# Smart_Driver_Adapter_PadMod.net
KiCad netlist of a schematic drawn in EAGLE
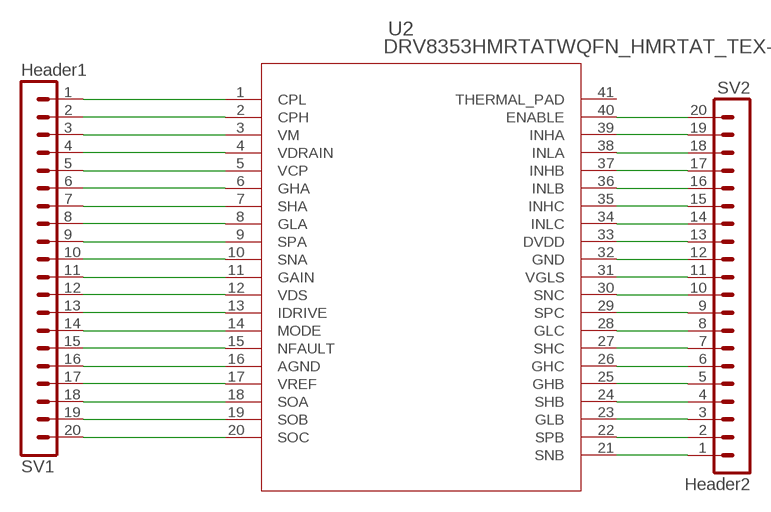
[diagram p0: schematic, sheet 1]

(export (version "E")
  (design (tool "Eeschema 10.0.6"))
  (components
    (comp (ref "SV1")
      (value "Header1")
      (footprint "eagle-import:MA20-1")
      (libsource (lib "eagle-import") (part "MA20-1"))
    )
    (comp (ref "SV2")
      (value "Header2")
      (footprint "eagle-import:MA20-1")
      (libsource (lib "eagle-import") (part "MA20-1"))
    )
    (comp (ref "U2")
      (value "DRV8353HMRTATWQFN_HMRTAT_TEX-M")
      (footprint "eagle-import:WQFN_HMRTAT_TEX-M")
      (fields
        (field (name "MANUFACTURER_PART_NUMBER") "DRV8353HMRTAT")
        (field (name "COPYRIGHT") "Copyright (C) 2021 Ultra Librarian. All rights reserved.")
      )
      (libsource (lib "eagle-import") (part "DRV8353HMRTATWQFN_HMRTAT_TEX-M"))
    )
  )
  (nets
    (net (code "1") (name "Net-(U2-AGND)") (class "Default")
      (node (ref "SV1") (pin "16") (pinfunction "16_16") (pintype "passive"))
      (node (ref "U2") (pin "16") (pinfunction "AGND_16") (pintype "passive"))
    )
    (net (code "2") (name "Net-(U2-CPH)") (class "Default")
      (node (ref "SV1") (pin "2") (pinfunction "2_2") (pintype "passive"))
      (node (ref "U2") (pin "2") (pinfunction "CPH_2") (pintype "passive"))
    )
    (net (code "3") (name "Net-(U2-CPL)") (class "Default")
      (node (ref "SV1") (pin "1") (pinfunction "1_1") (pintype "passive"))
      (node (ref "U2") (pin "1") (pinfunction "CPL_1") (pintype "passive"))
    )
    (net (code "4") (name "Net-(U2-DVDD)") (class "Default")
      (node (ref "SV2") (pin "13") (pinfunction "13_13") (pintype "passive"))
      (node (ref "U2") (pin "33") (pinfunction "DVDD_33") (pintype "power_in"))
    )
    (net (code "5") (name "Net-(U2-ENABLE)") (class "Default")
      (node (ref "SV2") (pin "20") (pinfunction "20_20") (pintype "passive"))
      (node (ref "U2") (pin "40") (pinfunction "ENABLE_40") (pintype "passive"))
    )
    (net (code "6") (name "Net-(U2-GAIN)") (class "Default")
      (node (ref "SV1") (pin "11") (pinfunction "11_11") (pintype "passive"))
      (node (ref "U2") (pin "11") (pinfunction "GAIN_11") (pintype "passive"))
    )
    (net (code "7") (name "Net-(U2-GHA)") (class "Default")
      (node (ref "SV1") (pin "6") (pinfunction "6_6") (pintype "passive"))
      (node (ref "U2") (pin "6") (pinfunction "GHA_6") (pintype "passive"))
    )
    (net (code "8") (name "Net-(U2-GHB)") (class "Default")
      (node (ref "SV2") (pin "5") (pinfunction "5_5") (pintype "passive"))
      (node (ref "U2") (pin "25") (pinfunction "GHB_25") (pintype "passive"))
    )
    (net (code "9") (name "Net-(U2-GHC)") (class "Default")
      (node (ref "SV2") (pin "6") (pinfunction "6_6") (pintype "passive"))
      (node (ref "U2") (pin "26") (pinfunction "GHC_26") (pintype "passive"))
    )
    (net (code "10") (name "Net-(U2-GLA)") (class "Default")
      (node (ref "SV1") (pin "8") (pinfunction "8_8") (pintype "passive"))
      (node (ref "U2") (pin "8") (pinfunction "GLA_8") (pintype "passive"))
    )
    (net (code "11") (name "Net-(U2-GLB)") (class "Default")
      (node (ref "SV2") (pin "3") (pinfunction "3_3") (pintype "passive"))
      (node (ref "U2") (pin "23") (pinfunction "GLB_23") (pintype "passive"))
    )
    (net (code "12") (name "Net-(U2-GLC)") (class "Default")
      (node (ref "SV2") (pin "8") (pinfunction "8_8") (pintype "passive"))
      (node (ref "U2") (pin "28") (pinfunction "GLC_28") (pintype "passive"))
    )
    (net (code "13") (name "Net-(U2-GND)") (class "Default")
      (node (ref "SV2") (pin "12") (pinfunction "12_12") (pintype "passive"))
      (node (ref "U2") (pin "32") (pinfunction "GND_32") (pintype "passive"))
    )
    (net (code "14") (name "Net-(U2-IDRIVE)") (class "Default")
      (node (ref "SV1") (pin "13") (pinfunction "13_13") (pintype "passive"))
      (node (ref "U2") (pin "13") (pinfunction "IDRIVE_13") (pintype "passive"))
    )
    (net (code "15") (name "Net-(U2-INHA)") (class "Default")
      (node (ref "SV2") (pin "19") (pinfunction "19_19") (pintype "passive"))
      (node (ref "U2") (pin "39") (pinfunction "INHA_39") (pintype "input"))
    )
    (net (code "16") (name "Net-(U2-INHB)") (class "Default")
      (node (ref "SV2") (pin "17") (pinfunction "17_17") (pintype "passive"))
      (node (ref "U2") (pin "37") (pinfunction "INHB_37") (pintype "input"))
    )
    (net (code "17") (name "Net-(U2-INHC)") (class "Default")
      (node (ref "SV2") (pin "15") (pinfunction "15_15") (pintype "passive"))
      (node (ref "U2") (pin "35") (pinfunction "INHC_35") (pintype "input"))
    )
    (net (code "18") (name "Net-(U2-INLA)") (class "Default")
      (node (ref "SV2") (pin "18") (pinfunction "18_18") (pintype "passive"))
      (node (ref "U2") (pin "38") (pinfunction "INLA_38") (pintype "input"))
    )
    (net (code "19") (name "Net-(U2-INLB)") (class "Default")
      (node (ref "SV2") (pin "16") (pinfunction "16_16") (pintype "passive"))
      (node (ref "U2") (pin "36") (pinfunction "INLB_36") (pintype "input"))
    )
    (net (code "20") (name "Net-(U2-INLC)") (class "Default")
      (node (ref "SV2") (pin "14") (pinfunction "14_14") (pintype "passive"))
      (node (ref "U2") (pin "34") (pinfunction "INLC_34") (pintype "input"))
    )
    (net (code "21") (name "Net-(U2-MODE)") (class "Default")
      (node (ref "SV1") (pin "14") (pinfunction "14_14") (pintype "passive"))
      (node (ref "U2") (pin "14") (pinfunction "MODE_14") (pintype "passive"))
    )
    (net (code "22") (name "Net-(U2-NFAULT)") (class "Default")
      (node (ref "SV1") (pin "15") (pinfunction "15_15") (pintype "passive"))
      (node (ref "U2") (pin "15") (pinfunction "NFAULT_15") (pintype "passive"))
    )
    (net (code "23") (name "Net-(U2-SHA)") (class "Default")
      (node (ref "SV1") (pin "7") (pinfunction "7_7") (pintype "passive"))
      (node (ref "U2") (pin "7") (pinfunction "SHA_7") (pintype "passive"))
    )
    (net (code "24") (name "Net-(U2-SHB)") (class "Default")
      (node (ref "SV2") (pin "4") (pinfunction "4_4") (pintype "passive"))
      (node (ref "U2") (pin "24") (pinfunction "SHB_24") (pintype "passive"))
    )
    (net (code "25") (name "Net-(U2-SHC)") (class "Default")
      (node (ref "SV2") (pin "7") (pinfunction "7_7") (pintype "passive"))
      (node (ref "U2") (pin "27") (pinfunction "SHC_27") (pintype "passive"))
    )
    (net (code "26") (name "Net-(U2-SNA)") (class "Default")
      (node (ref "SV1") (pin "10") (pinfunction "10_10") (pintype "passive"))
      (node (ref "U2") (pin "10") (pinfunction "SNA_10") (pintype "passive"))
    )
    (net (code "27") (name "Net-(U2-SNB)") (class "Default")
      (node (ref "SV2") (pin "1") (pinfunction "1_1") (pintype "passive"))
      (node (ref "U2") (pin "21") (pinfunction "SNB_21") (pintype "passive"))
    )
    (net (code "28") (name "Net-(U2-SNC)") (class "Default")
      (node (ref "SV2") (pin "10") (pinfunction "10_10") (pintype "passive"))
      (node (ref "U2") (pin "30") (pinfunction "SNC_30") (pintype "passive"))
    )
    (net (code "29") (name "Net-(U2-SOA)") (class "Default")
      (node (ref "SV1") (pin "18") (pinfunction "18_18") (pintype "passive"))
      (node (ref "U2") (pin "18") (pinfunction "SOA_18") (pintype "passive"))
    )
    (net (code "30") (name "Net-(U2-SOB)") (class "Default")
      (node (ref "SV1") (pin "19") (pinfunction "19_19") (pintype "passive"))
      (node (ref "U2") (pin "19") (pinfunction "SOB_19") (pintype "passive"))
    )
    (net (code "31") (name "Net-(U2-SOC)") (class "Default")
      (node (ref "SV1") (pin "20") (pinfunction "20_20") (pintype "passive"))
      (node (ref "U2") (pin "20") (pinfunction "SOC_20") (pintype "passive"))
    )
    (net (code "32") (name "Net-(U2-SPA)") (class "Default")
      (node (ref "SV1") (pin "9") (pinfunction "9_9") (pintype "passive"))
      (node (ref "U2") (pin "9") (pinfunction "SPA_9") (pintype "passive"))
    )
    (net (code "33") (name "Net-(U2-SPB)") (class "Default")
      (node (ref "SV2") (pin "2") (pinfunction "2_2") (pintype "passive"))
      (node (ref "U2") (pin "22") (pinfunction "SPB_22") (pintype "passive"))
    )
    (net (code "34") (name "Net-(U2-SPC)") (class "Default")
      (node (ref "SV2") (pin "9") (pinfunction "9_9") (pintype "passive"))
      (node (ref "U2") (pin "29") (pinfunction "SPC_29") (pintype "passive"))
    )
    (net (code "35") (name "Net-(U2-VCP)") (class "Default")
      (node (ref "SV1") (pin "5") (pinfunction "5_5") (pintype "passive"))
      (node (ref "U2") (pin "5") (pinfunction "VCP_5") (pintype "passive"))
    )
    (net (code "36") (name "Net-(U2-VDRAIN)") (class "Default")
      (node (ref "SV1") (pin "4") (pinfunction "4_4") (pintype "passive"))
      (node (ref "U2") (pin "4") (pinfunction "VDRAIN_4") (pintype "passive"))
    )
    (net (code "37") (name "Net-(U2-VDS)") (class "Default")
      (node (ref "SV1") (pin "12") (pinfunction "12_12") (pintype "passive"))
      (node (ref "U2") (pin "12") (pinfunction "VDS_12") (pintype "passive"))
    )
    (net (code "38") (name "Net-(U2-VGLS)") (class "Default")
      (node (ref "SV2") (pin "11") (pinfunction "11_11") (pintype "passive"))
      (node (ref "U2") (pin "31") (pinfunction "VGLS_31") (pintype "passive"))
    )
    (net (code "39") (name "Net-(U2-VM)") (class "Default")
      (node (ref "SV1") (pin "3") (pinfunction "3_3") (pintype "passive"))
      (node (ref "U2") (pin "3") (pinfunction "VM_3") (pintype "passive"))
    )
    (net (code "40") (name "Net-(U2-VREF)") (class "Default")
      (node (ref "SV1") (pin "17") (pinfunction "17_17") (pintype "passive"))
      (node (ref "U2") (pin "17") (pinfunction "VREF_17") (pintype "power_in"))
    )
    (net (code "41") (name "unconnected-(U2-THERMAL_PAD-Pad41)") (class "Default")
      (node (ref "U2") (pin "41") (pinfunction "THERMAL_PAD_41") (pintype "passive"))
    )
  )
)
